# SWD.net
KiCad netlist of a schematic drawn in Altium Designer
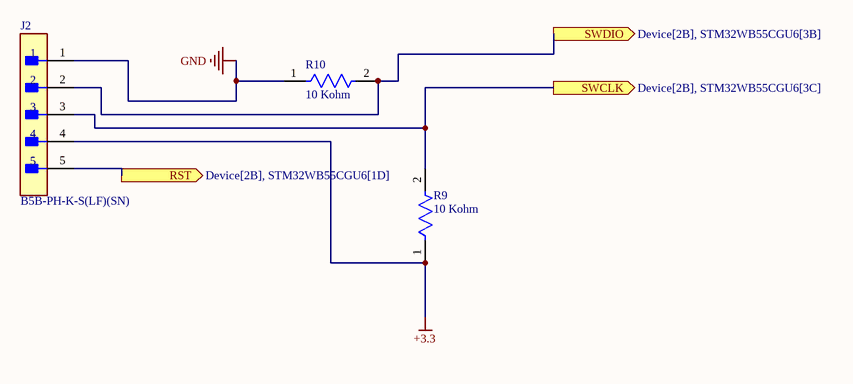
[diagram p0: SWD.SchDoc]

(export (version "E")
  (design (tool "Eeschema 10.0.6"))
  (components
    (comp (ref "J2")
      (value "B5B-PH-K-S(LF)(SN)")
      (footprint "FP-B5B-PH-K-S_LF_SN-MFG")
      (description "CONN HEADER VERT 5POS 2MM")
      (libsource (lib "Altium Content Vault") (part "bf93c07fd2649a848d0ec8585582aab"))
    )
    (comp (ref "R9")
      (value "10 Kohm")
      (footprint "FP-RC1005-IPC_C")
      (description "Res Thick Film 0402 1.87kΩ 1% 0.063W ±100ppm/°C Molded SMD T/R")
      (fields (field (name "TOLERANCE") "1%"))
      (libsource (lib "Altium Content Vault") (part "1029c3af85768c4190bb7ad29bc67b5"))
    )
    (comp (ref "R10")
      (value "10 Kohm")
      (footprint "FP-RC1005-IPC_C")
      (description "Res Thick Film 0402 1.87kΩ 1% 0.063W ±100ppm/°C Molded SMD T/R")
      (fields (field (name "TOLERANCE") "1%"))
      (libsource (lib "Altium Content Vault") (part "1029c3af85768c4190bb7ad29bc67b5"))
    )
  )
  (nets
    (net (code "1") (name "+3.3") (class "Default")
      (node (ref "J2") (pin "4") (pinfunction "4_4") (pintype "passive"))
      (node (ref "R9") (pin "1") (pinfunction "1_1") (pintype "passive"))
    )
    (net (code "2") (name "/RST") (class "Default")
      (node (ref "J2") (pin "5") (pinfunction "5_5") (pintype "passive"))
    )
    (net (code "3") (name "/SWCLK") (class "Default")
      (node (ref "J2") (pin "3") (pinfunction "3_3") (pintype "passive"))
      (node (ref "R9") (pin "2") (pinfunction "2_2") (pintype "passive"))
    )
    (net (code "4") (name "/SWDIO") (class "Default")
      (node (ref "J2") (pin "2") (pinfunction "2_2") (pintype "passive"))
      (node (ref "R10") (pin "2") (pinfunction "2_2") (pintype "passive"))
    )
    (net (code "5") (name "GND") (class "Default")
      (node (ref "J2") (pin "1") (pinfunction "1_1") (pintype "passive"))
      (node (ref "R10") (pin "1") (pinfunction "1_1") (pintype "passive"))
    )
  )
)
